# v5_DEF.net
KiCad netlist of a schematic drawn in EAGLE
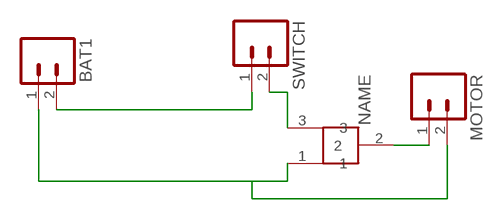
[diagram p0: schematic, sheet 1]

(export (version "E")
  (design (tool "Eeschema 10.0.6"))
  (components
    (comp (ref "BAT1")
      (value "M02-JST-2-PTH-NO_SILK")
      (footprint "eagle-import:JST-2-PTH-NS")
      (libsource (lib "eagle-import") (part "M02-JST-2-PTH-NO_SILK"))
    )
    (comp (ref "MOTOR")
      (value "M02-JST-2-PTH-NO_SILK")
      (footprint "eagle-import:JST-2-PTH-NS")
      (libsource (lib "eagle-import") (part "M02-JST-2-PTH-NO_SILK"))
    )
    (comp (ref "SWITCH")
      (value "M02-JST-2-PTH-NO_SILK")
      (footprint "eagle-import:JST-2-PTH-NS")
      (libsource (lib "eagle-import") (part "M02-JST-2-PTH-NO_SILK"))
    )
    (comp (ref "U$1")
      (value "BOURNS3313JBOURNS3313J")
      (footprint "eagle-import:BOURNS3313J")
      (libsource (lib "eagle-import") (part "BOURNS3313JBOURNS3313J"))
    )
  )
  (nets
    (net (code "1") (name "Net-(BAT1-Pad1)") (class "Default")
      (node (ref "BAT1") (pin "1") (pinfunction "1_1") (pintype "passive"))
      (node (ref "MOTOR") (pin "2") (pinfunction "2_2") (pintype "passive"))
      (node (ref "U$1") (pin "1") (pinfunction "1_1") (pintype "bidirectional"))
    )
    (net (code "2") (name "Net-(BAT1-Pad2)") (class "Default")
      (node (ref "BAT1") (pin "2") (pinfunction "2_2") (pintype "passive"))
      (node (ref "SWITCH") (pin "1") (pinfunction "1_1") (pintype "passive"))
    )
    (net (code "3") (name "Net-(MOTOR-Pad1)") (class "Default")
      (node (ref "MOTOR") (pin "1") (pinfunction "1_1") (pintype "passive"))
      (node (ref "U$1") (pin "2") (pinfunction "2_2") (pintype "bidirectional"))
    )
    (net (code "4") (name "Net-(SWITCH-Pad2)") (class "Default")
      (node (ref "SWITCH") (pin "2") (pinfunction "2_2") (pintype "passive"))
      (node (ref "U$1") (pin "3") (pinfunction "3_3") (pintype "bidirectional"))
    )
  )
)
